# FixedItFinalFinal.net
KiCad netlist of a schematic drawn in EAGLE
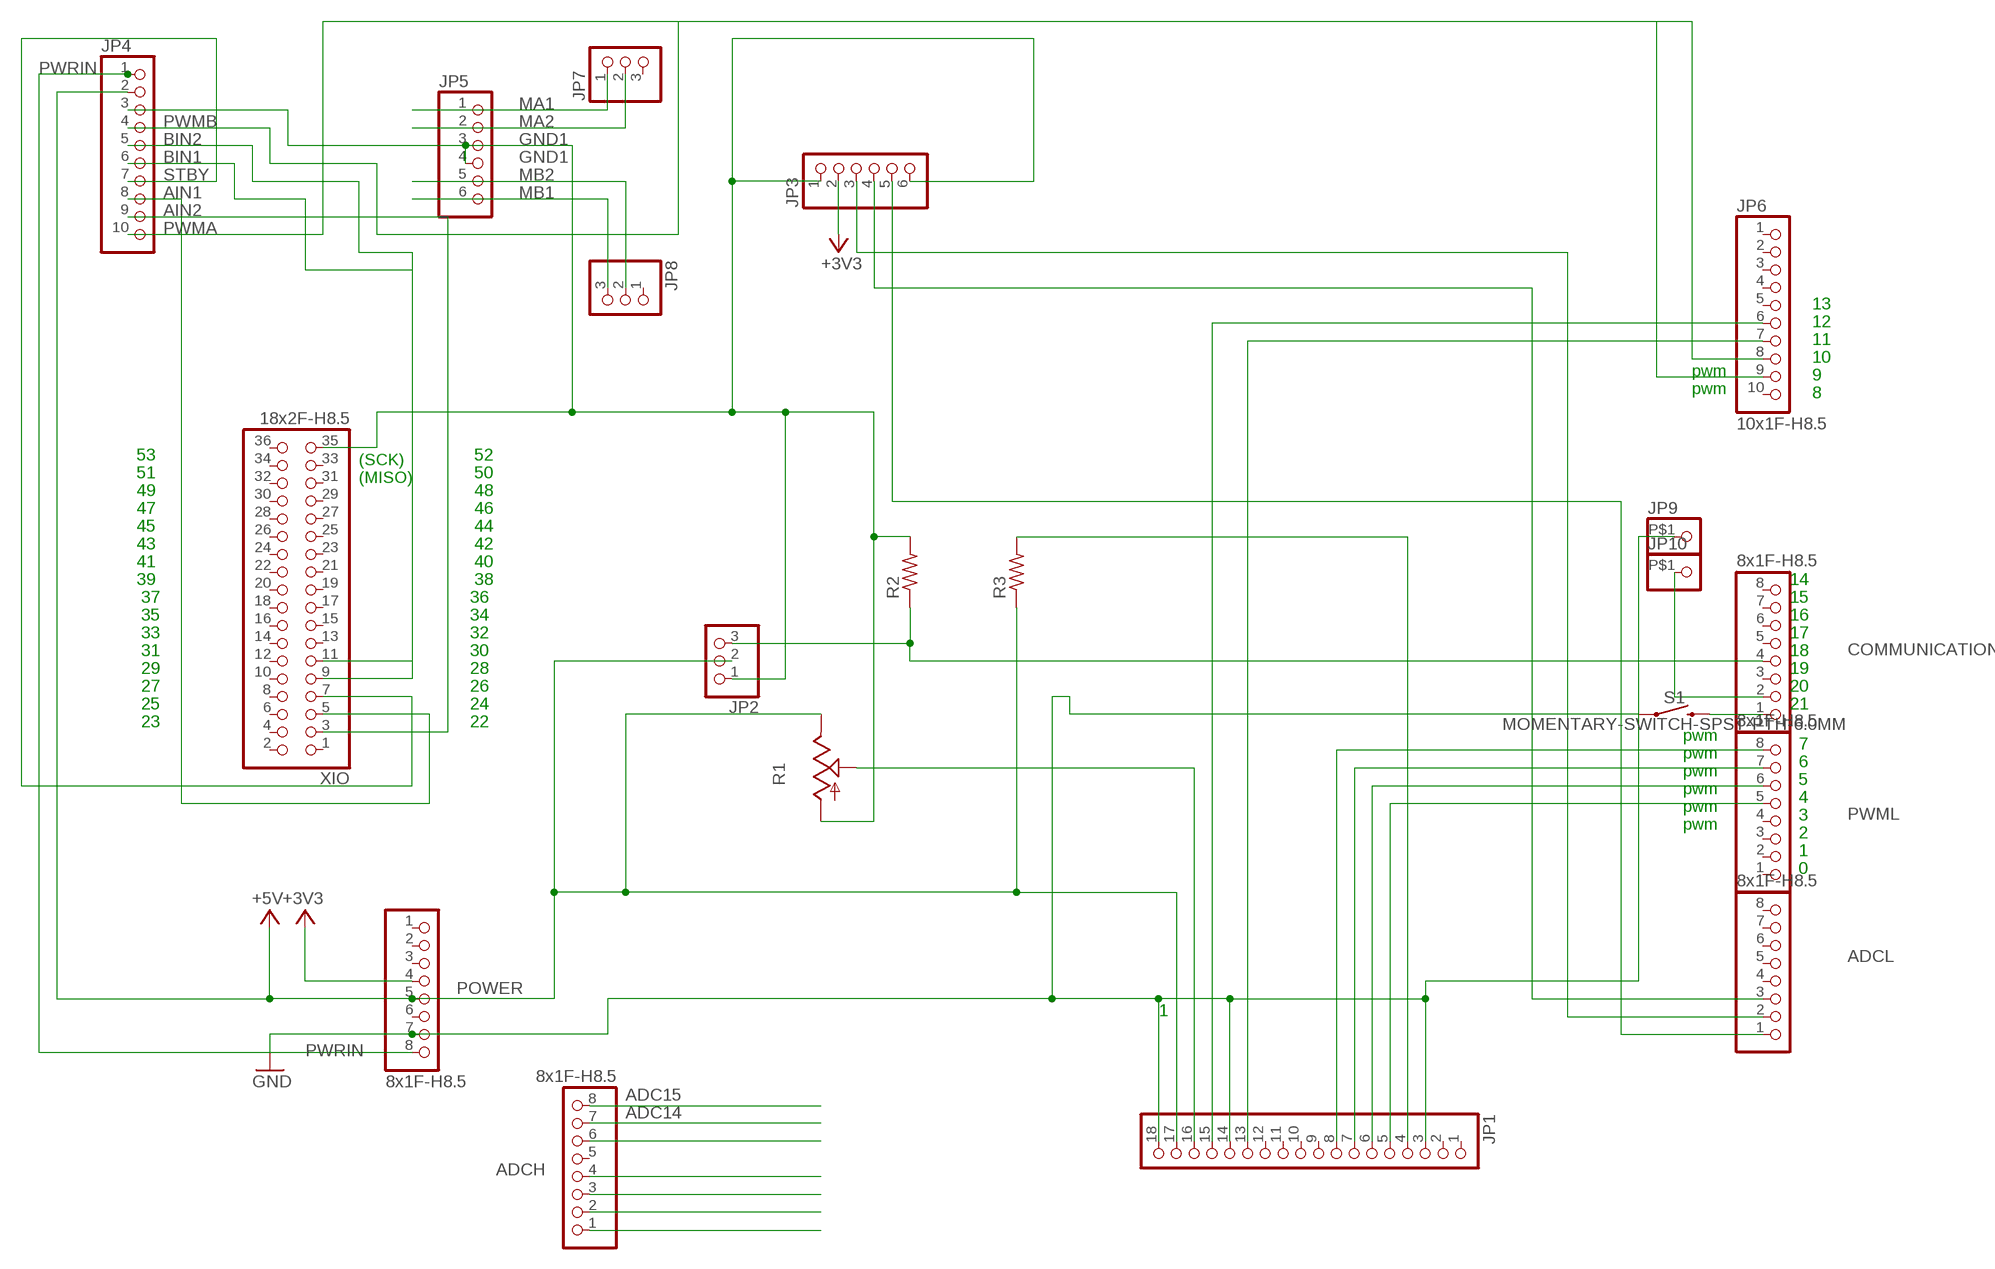
[diagram p0: schematic, sheet 1]

(export (version "E")
  (design (tool "Eeschema 10.0.6"))
  (components
    (comp (ref "ADCH")
      (value "8x1F-H8.5")
      (footprint "eagle-import:1X08")
      (libsource (lib "eagle-import") (part "PINHD-1X8"))
    )
    (comp (ref "ADCL")
      (value "8x1F-H8.5")
      (footprint "eagle-import:1X08")
      (libsource (lib "eagle-import") (part "PINHD-1X8"))
    )
    (comp (ref "COMMUNICATION")
      (value "8x1F-H8.5")
      (footprint "eagle-import:1X08")
      (libsource (lib "eagle-import") (part "PINHD-1X8"))
    )
    (comp (ref "JP1")
      (value "PINHD-1X18")
      (footprint "eagle-import:1X18")
      (libsource (lib "eagle-import") (part "PINHD-1X18"))
    )
    (comp (ref "JP2")
      (value "PINHD-1X3")
      (footprint "eagle-import:1X03")
      (libsource (lib "eagle-import") (part "PINHD-1X3"))
    )
    (comp (ref "JP3")
      (value "PINHD-1X6")
      (footprint "eagle-import:1X06")
      (libsource (lib "eagle-import") (part "adafruit_420_PINHD-1X6"))
    )
    (comp (ref "JP4")
      (value "HEADER-1X10THICKER")
      (footprint "eagle-import:1X10_ROUND_76")
      (libsource (lib "eagle-import") (part "HEADER-1X10THICKER"))
    )
    (comp (ref "JP5")
      (value "PINHD-1X6CB")
      (footprint "eagle-import:1X06-CLEANBIG")
      (libsource (lib "eagle-import") (part "PINHD-1X6CB"))
    )
    (comp (ref "JP6")
      (value "10x1F-H8.5")
      (footprint "eagle-import:1X10")
      (libsource (lib "eagle-import") (part "PINHD-1X10_ARD"))
    )
    (comp (ref "JP7")
      (value "PINHD-1X3")
      (footprint "eagle-import:1X03")
      (libsource (lib "eagle-import") (part "PINHD-1X3"))
    )
    (comp (ref "JP8")
      (value "PINHD-1X3")
      (footprint "eagle-import:1X03")
      (libsource (lib "eagle-import") (part "PINHD-1X3"))
    )
    (comp (ref "JP9")
      (value "PINHD-1X1-BIGPOGO")
      (footprint "eagle-import:1X1-BIGPOGO")
      (libsource (lib "eagle-import") (part "PINHD-1X1-BIGPOGO"))
    )
    (comp (ref "JP10")
      (value "PINHD-1X1-BIGPOGO")
      (footprint "eagle-import:1X1-BIGPOGO")
      (libsource (lib "eagle-import") (part "PINHD-1X1-BIGPOGO"))
    )
    (comp (ref "POWER")
      (value "8x1F-H8.5")
      (footprint "eagle-import:1X08")
      (libsource (lib "eagle-import") (part "PINHD-1X8"))
    )
    (comp (ref "PWML")
      (value "8x1F-H8.5")
      (footprint "eagle-import:1X08")
      (libsource (lib "eagle-import") (part "PINHD-1X8"))
    )
    (comp (ref "R1")
      (value "TRIM_US-RS3")
      (footprint "eagle-import:RS3")
      (libsource (lib "eagle-import") (part "TRIM_US-RS3"))
    )
    (comp (ref "R2")
      (value "R-US_0204/7")
      (footprint "eagle-import:0204_7")
      (libsource (lib "eagle-import") (part "R-US_0204/7"))
    )
    (comp (ref "R3")
      (value "R-US_0204/7")
      (footprint "eagle-import:0204_7")
      (libsource (lib "eagle-import") (part "R-US_0204/7"))
    )
    (comp (ref "S1")
      (value "MOMENTARY-SWITCH-SPST-PTH-6.0MM")
      (footprint "eagle-import:TACTILE_SWITCH_PTH_6.0MM")
      (libsource (lib "eagle-import") (part "MOMENTARY-SWITCH-SPST-PTH-6.0MM"))
    )
    (comp (ref "XIO")
      (value "18x2F-H8.5")
      (footprint "eagle-import:2X18")
      (libsource (lib "eagle-import") (part "PINHD-2X18"))
    )
  )
  (nets
    (net (code "1") (name "+3V3") (class "Default")
      (node (ref "JP3") (pin "2") (pinfunction "2_2") (pintype "passive"))
      (node (ref "POWER") (pin "4") (pinfunction "4_4") (pintype "passive"))
    )
    (net (code "2") (name "+5V") (class "Default")
      (node (ref "JP1") (pin "17") (pinfunction "17_17") (pintype "passive"))
      (node (ref "JP2") (pin "2") (pinfunction "2_2") (pintype "passive"))
      (node (ref "JP4") (pin "2") (pinfunction "2_2") (pintype "passive"))
      (node (ref "POWER") (pin "5") (pinfunction "5_5") (pintype "passive"))
      (node (ref "R1") (pin "E") (pinfunction "E_E") (pintype "passive"))
      (node (ref "R3") (pin "1") (pinfunction "1_1") (pintype "passive"))
    )
    (net (code "3") (name "/ADC14") (class "Default")
      (node (ref "ADCH") (pin "7") (pinfunction "7_7") (pintype "passive"))
    )
    (net (code "4") (name "/ADC15") (class "Default")
      (node (ref "ADCH") (pin "8") (pinfunction "8_8") (pintype "passive"))
    )
    (net (code "5") (name "/AIN1") (class "Default")
      (node (ref "JP4") (pin "8") (pinfunction "8_8") (pintype "passive"))
      (node (ref "XIO") (pin "5") (pinfunction "5_5") (pintype "passive"))
    )
    (net (code "6") (name "/AIN2") (class "Default")
      (node (ref "JP4") (pin "9") (pinfunction "9_9") (pintype "passive"))
      (node (ref "XIO") (pin "3") (pinfunction "3_3") (pintype "passive"))
    )
    (net (code "7") (name "/BIN1") (class "Default")
      (node (ref "JP4") (pin "6") (pinfunction "6_6") (pintype "passive"))
      (node (ref "XIO") (pin "9") (pinfunction "9_9") (pintype "passive"))
    )
    (net (code "8") (name "/BIN2") (class "Default")
      (node (ref "JP4") (pin "5") (pinfunction "5_5") (pintype "passive"))
      (node (ref "XIO") (pin "11") (pinfunction "11_11") (pintype "passive"))
    )
    (net (code "9") (name "/GND1") (class "Default")
      (node (ref "JP2") (pin "1") (pinfunction "1_1") (pintype "passive"))
      (node (ref "JP3") (pin "1") (pinfunction "1_1") (pintype "passive"))
      (node (ref "JP3") (pin "6") (pinfunction "6_6") (pintype "passive"))
      (node (ref "JP4") (pin "3") (pinfunction "3_3") (pintype "passive"))
      (node (ref "JP5") (pin "3") (pinfunction "3_3") (pintype "passive"))
      (node (ref "JP5") (pin "4") (pinfunction "4_4") (pintype "passive"))
      (node (ref "R1") (pin "A") (pinfunction "A_A") (pintype "passive"))
      (node (ref "R2") (pin "2") (pinfunction "2_2") (pintype "passive"))
      (node (ref "XIO") (pin "35") (pinfunction "35_35") (pintype "passive"))
    )
    (net (code "10") (name "/MA1") (class "Default")
      (node (ref "JP5") (pin "1") (pinfunction "1_1") (pintype "passive"))
      (node (ref "JP7") (pin "1") (pinfunction "1_1") (pintype "passive"))
    )
    (net (code "11") (name "/MA2") (class "Default")
      (node (ref "JP5") (pin "2") (pinfunction "2_2") (pintype "passive"))
      (node (ref "JP7") (pin "2") (pinfunction "2_2") (pintype "passive"))
    )
    (net (code "12") (name "/MB1") (class "Default")
      (node (ref "JP5") (pin "6") (pinfunction "6_6") (pintype "passive"))
      (node (ref "JP8") (pin "3") (pinfunction "3_3") (pintype "passive"))
    )
    (net (code "13") (name "/MB2") (class "Default")
      (node (ref "JP5") (pin "5") (pinfunction "5_5") (pintype "passive"))
      (node (ref "JP8") (pin "2") (pinfunction "2_2") (pintype "passive"))
    )
    (net (code "14") (name "/PWMA") (class "Default")
      (node (ref "JP4") (pin "10") (pinfunction "10_10") (pintype "passive"))
      (node (ref "JP6") (pin "8") (pinfunction "8_8") (pintype "passive"))
    )
    (net (code "15") (name "/PWMB") (class "Default")
      (node (ref "JP4") (pin "4") (pinfunction "4_4") (pintype "passive"))
      (node (ref "JP6") (pin "9") (pinfunction "9_9") (pintype "passive"))
    )
    (net (code "16") (name "/PWRIN") (class "Default")
      (node (ref "JP4") (pin "1") (pinfunction "1_1") (pintype "passive"))
      (node (ref "POWER") (pin "8") (pinfunction "8_8") (pintype "passive"))
    )
    (net (code "17") (name "/STBY") (class "Default")
      (node (ref "JP4") (pin "7") (pinfunction "7_7") (pintype "passive"))
      (node (ref "XIO") (pin "7") (pinfunction "7_7") (pintype "passive"))
    )
    (net (code "18") (name "GND") (class "Default")
      (node (ref "JP1") (pin "14") (pinfunction "14_14") (pintype "passive"))
      (node (ref "JP1") (pin "18") (pinfunction "18_18") (pintype "passive"))
      (node (ref "JP1") (pin "3") (pinfunction "3_3") (pintype "passive"))
      (node (ref "JP9") (pin "P$1") (pinfunction "1_P$1") (pintype "passive"))
      (node (ref "POWER") (pin "7") (pinfunction "7_7") (pintype "passive"))
      (node (ref "S1") (pin "1") (pinfunction "1_1") (pintype "passive"))
    )
    (net (code "19") (name "Net-(ADCL-Pad1)") (class "Default")
      (node (ref "ADCL") (pin "1") (pinfunction "1_1") (pintype "passive"))
      (node (ref "JP3") (pin "5") (pinfunction "5_5") (pintype "passive"))
    )
    (net (code "20") (name "Net-(ADCL-Pad2)") (class "Default")
      (node (ref "ADCL") (pin "2") (pinfunction "2_2") (pintype "passive"))
      (node (ref "JP3") (pin "3") (pinfunction "3_3") (pintype "passive"))
    )
    (net (code "21") (name "Net-(ADCL-Pad3)") (class "Default")
      (node (ref "ADCL") (pin "3") (pinfunction "3_3") (pintype "passive"))
      (node (ref "JP3") (pin "4") (pinfunction "4_4") (pintype "passive"))
    )
    (net (code "22") (name "Net-(COMMUNICATION-Pad4)") (class "Default")
      (node (ref "COMMUNICATION") (pin "4") (pinfunction "4_4") (pintype "passive"))
      (node (ref "JP2") (pin "3") (pinfunction "3_3") (pintype "passive"))
      (node (ref "R2") (pin "1") (pinfunction "1_1") (pintype "passive"))
    )
    (net (code "23") (name "Net-(JP1-Pad4)") (class "Default")
      (node (ref "JP1") (pin "4") (pinfunction "4_4") (pintype "passive"))
      (node (ref "R3") (pin "2") (pinfunction "2_2") (pintype "passive"))
    )
    (net (code "24") (name "Net-(JP1-Pad5)") (class "Default")
      (node (ref "JP1") (pin "5") (pinfunction "5_5") (pintype "passive"))
      (node (ref "PWML") (pin "5") (pinfunction "5_5") (pintype "passive"))
    )
    (net (code "25") (name "Net-(JP1-Pad6)") (class "Default")
      (node (ref "JP1") (pin "6") (pinfunction "6_6") (pintype "passive"))
      (node (ref "PWML") (pin "6") (pinfunction "6_6") (pintype "passive"))
    )
    (net (code "26") (name "Net-(JP1-Pad7)") (class "Default")
      (node (ref "JP1") (pin "7") (pinfunction "7_7") (pintype "passive"))
      (node (ref "PWML") (pin "7") (pinfunction "7_7") (pintype "passive"))
    )
    (net (code "27") (name "Net-(JP1-Pad8)") (class "Default")
      (node (ref "JP1") (pin "8") (pinfunction "8_8") (pintype "passive"))
      (node (ref "PWML") (pin "8") (pinfunction "8_8") (pintype "passive"))
    )
    (net (code "28") (name "Net-(JP1-Pad13)") (class "Default")
      (node (ref "JP1") (pin "13") (pinfunction "13_13") (pintype "passive"))
      (node (ref "JP6") (pin "7") (pinfunction "7_7") (pintype "passive"))
    )
    (net (code "29") (name "Net-(JP1-Pad15)") (class "Default")
      (node (ref "JP1") (pin "15") (pinfunction "15_15") (pintype "passive"))
      (node (ref "JP6") (pin "6") (pinfunction "6_6") (pintype "passive"))
    )
    (net (code "30") (name "Net-(JP1-Pad16)") (class "Default")
      (node (ref "JP1") (pin "16") (pinfunction "16_16") (pintype "passive"))
      (node (ref "R1") (pin "S") (pinfunction "S_S") (pintype "passive"))
    )
    (net (code "31") (name "Net-(JP10-1)") (class "Default")
      (node (ref "COMMUNICATION") (pin "2") (pinfunction "2_2") (pintype "passive"))
      (node (ref "JP10") (pin "P$1") (pinfunction "1_P$1") (pintype "passive"))
    )
    (net (code "32") (name "Net-(S1-2)") (class "Default")
      (node (ref "COMMUNICATION") (pin "1") (pinfunction "1_1") (pintype "passive"))
      (node (ref "S1") (pin "3") (pinfunction "2_3") (pintype "passive"))
    )
    (net (code "33") (name "unconnected-(ADCH-Pad1)") (class "Default")
      (node (ref "ADCH") (pin "1") (pinfunction "1_1") (pintype "passive"))
    )
    (net (code "34") (name "unconnected-(ADCH-Pad2)") (class "Default")
      (node (ref "ADCH") (pin "2") (pinfunction "2_2") (pintype "passive"))
    )
    (net (code "35") (name "unconnected-(ADCH-Pad3)") (class "Default")
      (node (ref "ADCH") (pin "3") (pinfunction "3_3") (pintype "passive"))
    )
    (net (code "36") (name "unconnected-(ADCH-Pad4)") (class "Default")
      (node (ref "ADCH") (pin "4") (pinfunction "4_4") (pintype "passive"))
    )
    (net (code "37") (name "unconnected-(ADCH-Pad5)") (class "Default")
      (node (ref "ADCH") (pin "5") (pinfunction "5_5") (pintype "passive"))
    )
    (net (code "38") (name "unconnected-(ADCH-Pad6)") (class "Default")
      (node (ref "ADCH") (pin "6") (pinfunction "6_6") (pintype "passive"))
    )
    (net (code "39") (name "unconnected-(ADCL-Pad4)") (class "Default")
      (node (ref "ADCL") (pin "4") (pinfunction "4_4") (pintype "passive"))
    )
    (net (code "40") (name "unconnected-(ADCL-Pad5)") (class "Default")
      (node (ref "ADCL") (pin "5") (pinfunction "5_5") (pintype "passive"))
    )
    (net (code "41") (name "unconnected-(ADCL-Pad6)") (class "Default")
      (node (ref "ADCL") (pin "6") (pinfunction "6_6") (pintype "passive"))
    )
    (net (code "42") (name "unconnected-(ADCL-Pad7)") (class "Default")
      (node (ref "ADCL") (pin "7") (pinfunction "7_7") (pintype "passive"))
    )
    (net (code "43") (name "unconnected-(ADCL-Pad8)") (class "Default")
      (node (ref "ADCL") (pin "8") (pinfunction "8_8") (pintype "passive"))
    )
    (net (code "44") (name "unconnected-(COMMUNICATION-Pad3)") (class "Default")
      (node (ref "COMMUNICATION") (pin "3") (pinfunction "3_3") (pintype "passive"))
    )
    (net (code "45") (name "unconnected-(COMMUNICATION-Pad5)") (class "Default")
      (node (ref "COMMUNICATION") (pin "5") (pinfunction "5_5") (pintype "passive"))
    )
    (net (code "46") (name "unconnected-(COMMUNICATION-Pad6)") (class "Default")
      (node (ref "COMMUNICATION") (pin "6") (pinfunction "6_6") (pintype "passive"))
    )
    (net (code "47") (name "unconnected-(COMMUNICATION-Pad7)") (class "Default")
      (node (ref "COMMUNICATION") (pin "7") (pinfunction "7_7") (pintype "passive"))
    )
    (net (code "48") (name "unconnected-(COMMUNICATION-Pad8)") (class "Default")
      (node (ref "COMMUNICATION") (pin "8") (pinfunction "8_8") (pintype "passive"))
    )
    (net (code "49") (name "unconnected-(JP1-Pad1)") (class "Default")
      (node (ref "JP1") (pin "1") (pinfunction "1_1") (pintype "passive"))
    )
    (net (code "50") (name "unconnected-(JP1-Pad2)") (class "Default")
      (node (ref "JP1") (pin "2") (pinfunction "2_2") (pintype "passive"))
    )
    (net (code "51") (name "unconnected-(JP1-Pad9)") (class "Default")
      (node (ref "JP1") (pin "9") (pinfunction "9_9") (pintype "passive"))
    )
    (net (code "52") (name "unconnected-(JP1-Pad10)") (class "Default")
      (node (ref "JP1") (pin "10") (pinfunction "10_10") (pintype "passive"))
    )
    (net (code "53") (name "unconnected-(JP1-Pad11)") (class "Default")
      (node (ref "JP1") (pin "11") (pinfunction "11_11") (pintype "passive"))
    )
    (net (code "54") (name "unconnected-(JP1-Pad12)") (class "Default")
      (node (ref "JP1") (pin "12") (pinfunction "12_12") (pintype "passive"))
    )
    (net (code "55") (name "unconnected-(JP6-Pad1)") (class "Default")
      (node (ref "JP6") (pin "1") (pinfunction "1_1") (pintype "passive"))
    )
    (net (code "56") (name "unconnected-(JP6-Pad2)") (class "Default")
      (node (ref "JP6") (pin "2") (pinfunction "2_2") (pintype "passive"))
    )
    (net (code "57") (name "unconnected-(JP6-Pad3)") (class "Default")
      (node (ref "JP6") (pin "3") (pinfunction "3_3") (pintype "passive"))
    )
    (net (code "58") (name "unconnected-(JP6-Pad4)") (class "Default")
      (node (ref "JP6") (pin "4") (pinfunction "4_4") (pintype "passive"))
    )
    (net (code "59") (name "unconnected-(JP6-Pad5)") (class "Default")
      (node (ref "JP6") (pin "5") (pinfunction "5_5") (pintype "passive"))
    )
    (net (code "60") (name "unconnected-(JP6-Pad10)") (class "Default")
      (node (ref "JP6") (pin "10") (pinfunction "10_10") (pintype "passive"))
    )
    (net (code "61") (name "unconnected-(JP7-Pad3)") (class "Default")
      (node (ref "JP7") (pin "3") (pinfunction "3_3") (pintype "passive"))
    )
    (net (code "62") (name "unconnected-(JP8-Pad1)") (class "Default")
      (node (ref "JP8") (pin "1") (pinfunction "1_1") (pintype "passive"))
    )
    (net (code "63") (name "unconnected-(POWER-Pad1)") (class "Default")
      (node (ref "POWER") (pin "1") (pinfunction "1_1") (pintype "passive"))
    )
    (net (code "64") (name "unconnected-(POWER-Pad2)") (class "Default")
      (node (ref "POWER") (pin "2") (pinfunction "2_2") (pintype "passive"))
    )
    (net (code "65") (name "unconnected-(POWER-Pad3)") (class "Default")
      (node (ref "POWER") (pin "3") (pinfunction "3_3") (pintype "passive"))
    )
    (net (code "66") (name "unconnected-(POWER-Pad6)") (class "Default")
      (node (ref "POWER") (pin "6") (pinfunction "6_6") (pintype "passive"))
    )
    (net (code "67") (name "unconnected-(PWML-Pad1)") (class "Default")
      (node (ref "PWML") (pin "1") (pinfunction "1_1") (pintype "passive"))
    )
    (net (code "68") (name "unconnected-(PWML-Pad2)") (class "Default")
      (node (ref "PWML") (pin "2") (pinfunction "2_2") (pintype "passive"))
    )
    (net (code "69") (name "unconnected-(PWML-Pad3)") (class "Default")
      (node (ref "PWML") (pin "3") (pinfunction "3_3") (pintype "passive"))
    )
    (net (code "70") (name "unconnected-(PWML-Pad4)") (class "Default")
      (node (ref "PWML") (pin "4") (pinfunction "4_4") (pintype "passive"))
    )
    (net (code "71") (name "unconnected-(XIO-Pad1)") (class "Default")
      (node (ref "XIO") (pin "1") (pinfunction "1_1") (pintype "passive"))
    )
    (net (code "72") (name "unconnected-(XIO-Pad2)") (class "Default")
      (node (ref "XIO") (pin "2") (pinfunction "2_2") (pintype "passive"))
    )
    (net (code "73") (name "unconnected-(XIO-Pad4)") (class "Default")
      (node (ref "XIO") (pin "4") (pinfunction "4_4") (pintype "passive"))
    )
    (net (code "74") (name "unconnected-(XIO-Pad6)") (class "Default")
      (node (ref "XIO") (pin "6") (pinfunction "6_6") (pintype "passive"))
    )
    (net (code "75") (name "unconnected-(XIO-Pad8)") (class "Default")
      (node (ref "XIO") (pin "8") (pinfunction "8_8") (pintype "passive"))
    )
    (net (code "76") (name "unconnected-(XIO-Pad10)") (class "Default")
      (node (ref "XIO") (pin "10") (pinfunction "10_10") (pintype "passive"))
    )
    (net (code "77") (name "unconnected-(XIO-Pad12)") (class "Default")
      (node (ref "XIO") (pin "12") (pinfunction "12_12") (pintype "passive"))
    )
    (net (code "78") (name "unconnected-(XIO-Pad13)") (class "Default")
      (node (ref "XIO") (pin "13") (pinfunction "13_13") (pintype "passive"))
    )
    (net (code "79") (name "unconnected-(XIO-Pad14)") (class "Default")
      (node (ref "XIO") (pin "14") (pinfunction "14_14") (pintype "passive"))
    )
    (net (code "80") (name "unconnected-(XIO-Pad15)") (class "Default")
      (node (ref "XIO") (pin "15") (pinfunction "15_15") (pintype "passive"))
    )
    (net (code "81") (name "unconnected-(XIO-Pad16)") (class "Default")
      (node (ref "XIO") (pin "16") (pinfunction "16_16") (pintype "passive"))
    )
    (net (code "82") (name "unconnected-(XIO-Pad17)") (class "Default")
      (node (ref "XIO") (pin "17") (pinfunction "17_17") (pintype "passive"))
    )
    (net (code "83") (name "unconnected-(XIO-Pad18)") (class "Default")
      (node (ref "XIO") (pin "18") (pinfunction "18_18") (pintype "passive"))
    )
    (net (code "84") (name "unconnected-(XIO-Pad19)") (class "Default")
      (node (ref "XIO") (pin "19") (pinfunction "19_19") (pintype "passive"))
    )
    (net (code "85") (name "unconnected-(XIO-Pad20)") (class "Default")
      (node (ref "XIO") (pin "20") (pinfunction "20_20") (pintype "passive"))
    )
    (net (code "86") (name "unconnected-(XIO-Pad21)") (class "Default")
      (node (ref "XIO") (pin "21") (pinfunction "21_21") (pintype "passive"))
    )
    (net (code "87") (name "unconnected-(XIO-Pad22)") (class "Default")
      (node (ref "XIO") (pin "22") (pinfunction "22_22") (pintype "passive"))
    )
    (net (code "88") (name "unconnected-(XIO-Pad23)") (class "Default")
      (node (ref "XIO") (pin "23") (pinfunction "23_23") (pintype "passive"))
    )
    (net (code "89") (name "unconnected-(XIO-Pad24)") (class "Default")
      (node (ref "XIO") (pin "24") (pinfunction "24_24") (pintype "passive"))
    )
    (net (code "90") (name "unconnected-(XIO-Pad25)") (class "Default")
      (node (ref "XIO") (pin "25") (pinfunction "25_25") (pintype "passive"))
    )
    (net (code "91") (name "unconnected-(XIO-Pad26)") (class "Default")
      (node (ref "XIO") (pin "26") (pinfunction "26_26") (pintype "passive"))
    )
    (net (code "92") (name "unconnected-(XIO-Pad27)") (class "Default")
      (node (ref "XIO") (pin "27") (pinfunction "27_27") (pintype "passive"))
    )
    (net (code "93") (name "unconnected-(XIO-Pad28)") (class "Default")
      (node (ref "XIO") (pin "28") (pinfunction "28_28") (pintype "passive"))
    )
    (net (code "94") (name "unconnected-(XIO-Pad29)") (class "Default")
      (node (ref "XIO") (pin "29") (pinfunction "29_29") (pintype "passive"))
    )
    (net (code "95") (name "unconnected-(XIO-Pad30)") (class "Default")
      (node (ref "XIO") (pin "30") (pinfunction "30_30") (pintype "passive"))
    )
    (net (code "96") (name "unconnected-(XIO-Pad31)") (class "Default")
      (node (ref "XIO") (pin "31") (pinfunction "31_31") (pintype "passive"))
    )
    (net (code "97") (name "unconnected-(XIO-Pad32)") (class "Default")
      (node (ref "XIO") (pin "32") (pinfunction "32_32") (pintype "passive"))
    )
    (net (code "98") (name "unconnected-(XIO-Pad33)") (class "Default")
      (node (ref "XIO") (pin "33") (pinfunction "33_33") (pintype "passive"))
    )
    (net (code "99") (name "unconnected-(XIO-Pad34)") (class "Default")
      (node (ref "XIO") (pin "34") (pinfunction "34_34") (pintype "passive"))
    )
    (net (code "100") (name "unconnected-(XIO-Pad36)") (class "Default")
      (node (ref "XIO") (pin "36") (pinfunction "36_36") (pintype "passive"))
    )
  )
)
